# 1_MCU_IOBANK.net
KiCad netlist of a schematic drawn in Altium Designer
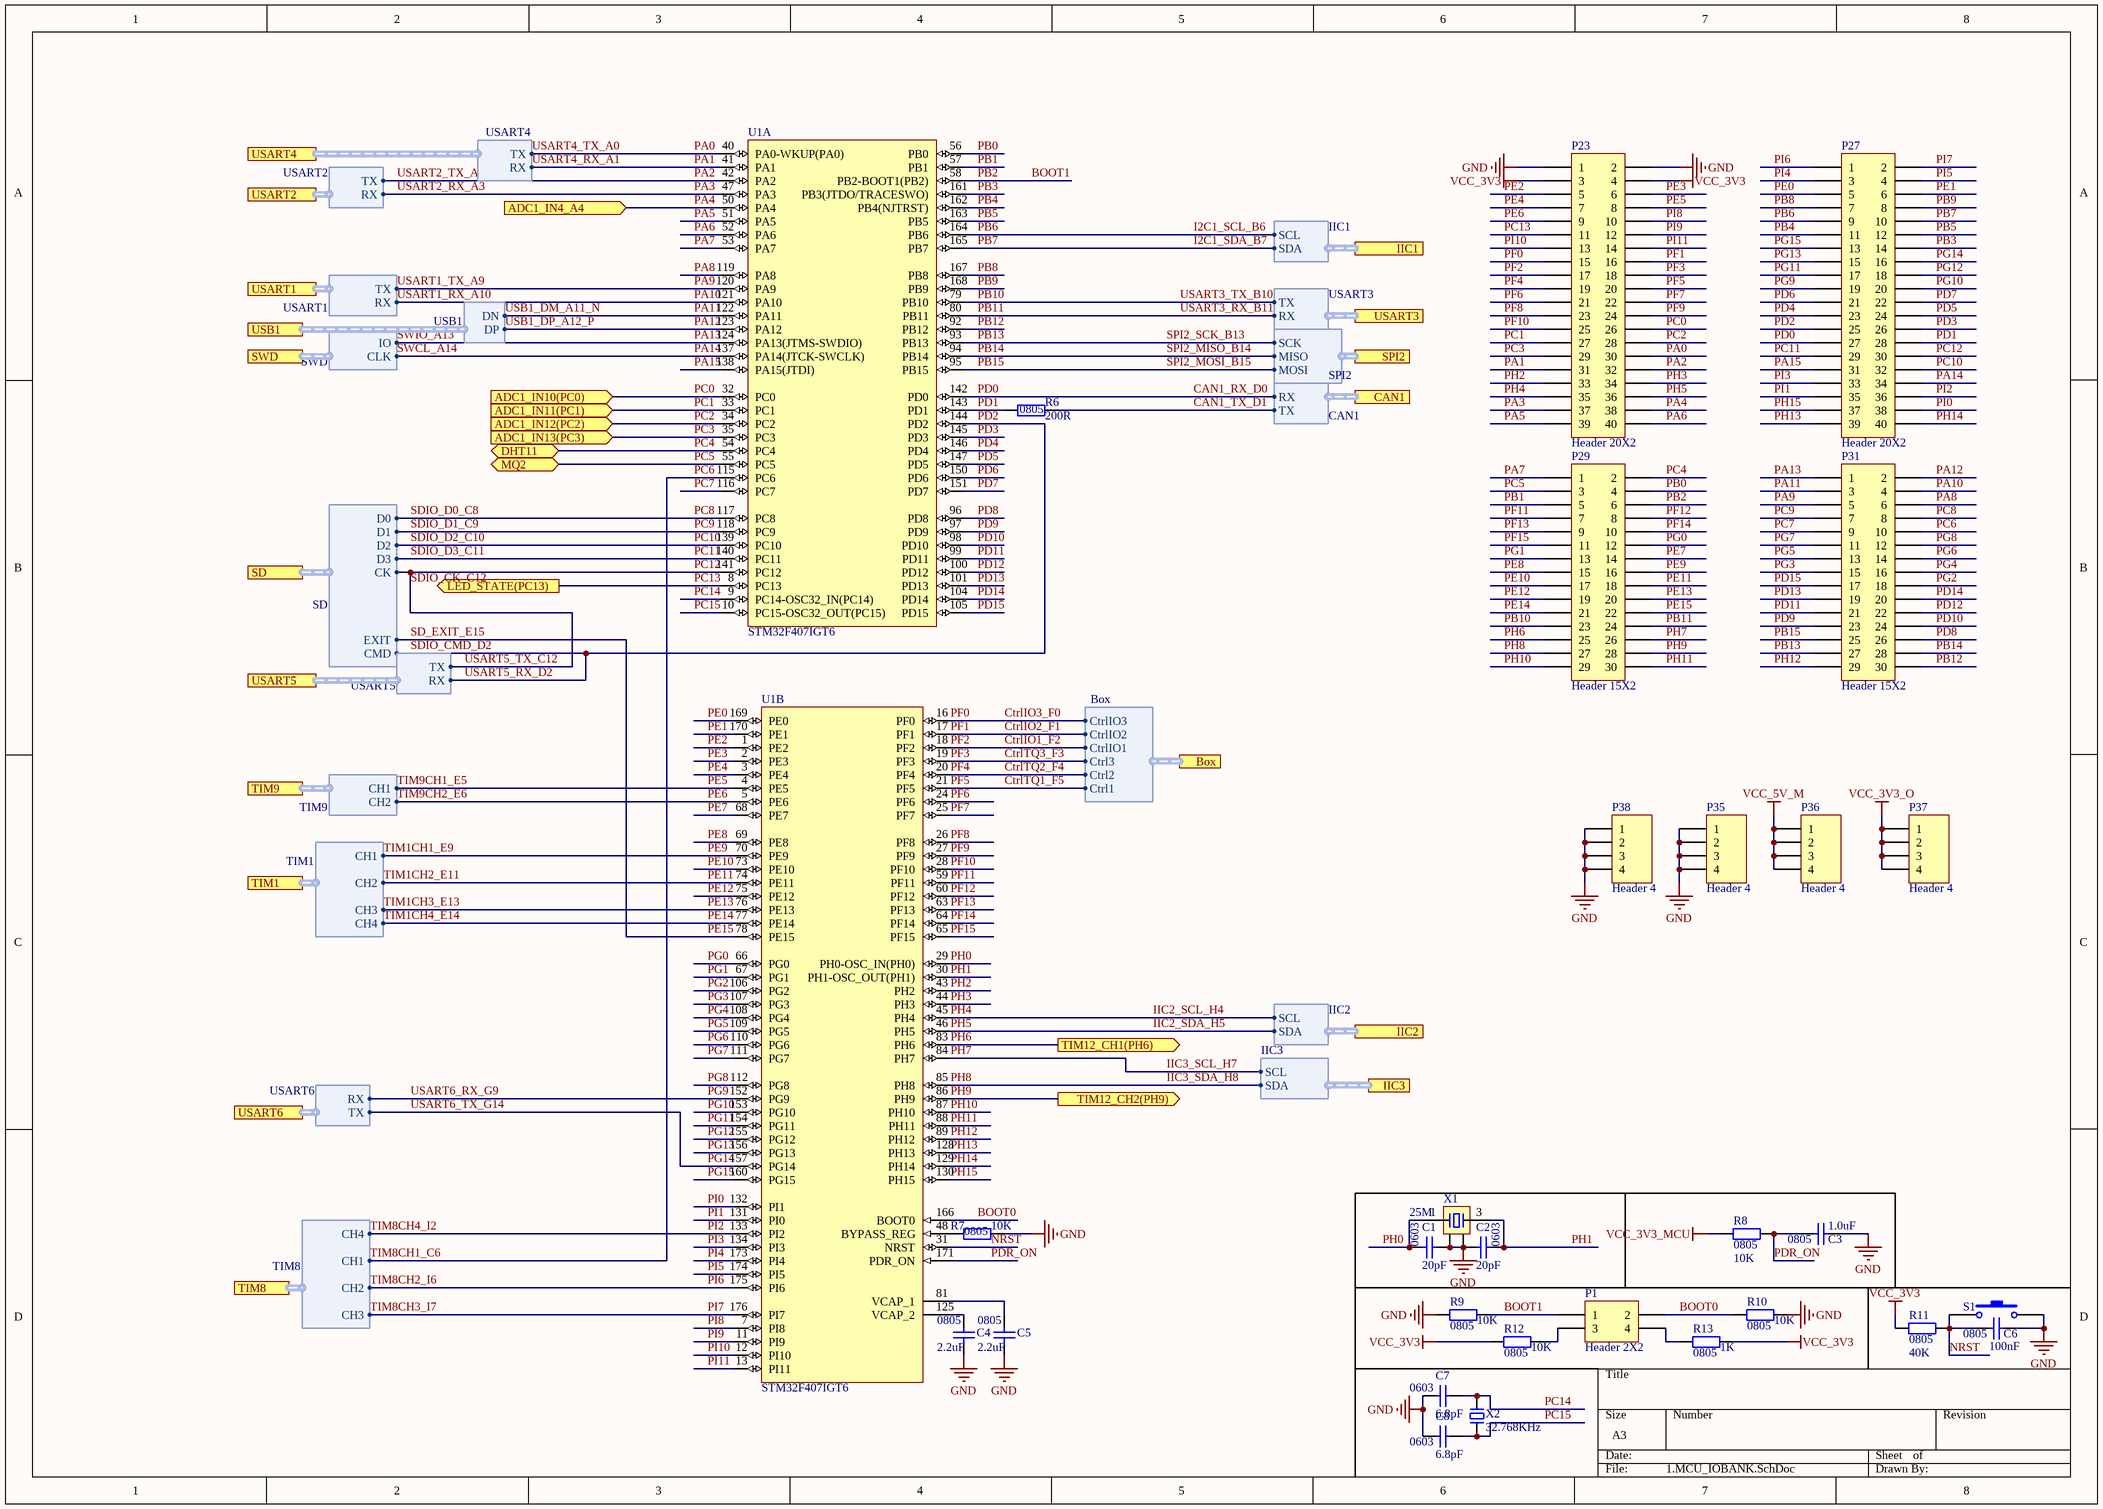
[diagram p0: 1.MCU_IOBANK.SchDoc]

(export (version "E")
  (design (tool "Eeschema 10.0.6"))
  (components
    (comp (ref "C1")
      (value "0603")
      (footprint "C 0603_L")
      (fields (field (name "ALTIUM_VALUE") "20pF"))
      (libsource (lib "QT") (part "CAP"))
    )
    (comp (ref "C2")
      (value "0603")
      (footprint "C 0603_L")
      (fields (field (name "ALTIUM_VALUE") "20pF"))
      (libsource (lib "QT") (part "CAP"))
    )
    (comp (ref "C3")
      (value "0805")
      (footprint "C 0805_M")
      (fields (field (name "ALTIUM_VALUE") "1.0uF"))
      (libsource (lib "QT") (part "CAP"))
    )
    (comp (ref "C4")
      (value "0805")
      (footprint "C 0805_M")
      (fields (field (name "ALTIUM_VALUE") "2.2uF"))
      (libsource (lib "QT") (part "CAP"))
    )
    (comp (ref "C5")
      (value "0805")
      (footprint "C 0805_M")
      (fields (field (name "ALTIUM_VALUE") "2.2uF"))
      (libsource (lib "QT") (part "CAP"))
    )
    (comp (ref "C6")
      (value "0805")
      (footprint "C 0805_M")
      (fields (field (name "ALTIUM_VALUE") "100nF"))
      (libsource (lib "QT") (part "CAP"))
    )
    (comp (ref "C7")
      (value "0603")
      (footprint "C 0603_M")
      (fields (field (name "ALTIUM_VALUE") "6.8pF"))
      (libsource (lib "QT") (part "CAP"))
    )
    (comp (ref "C8")
      (value "0603")
      (footprint "C 0603_L")
      (fields (field (name "ALTIUM_VALUE") "6.8pF"))
      (libsource (lib "QT") (part "CAP"))
    )
    (comp (ref "P1")
      (value "Header 2X2")
      (footprint "HDR2.54-LI-2x2P")
      (description "Header, 2-Pin, Dual row")
      (fields (field (name "PUBLISHER") "Altium Limited"))
      (libsource (lib "QT") (part "Header 2X2"))
    )
    (comp (ref "P23")
      (value "Header 20X2")
      (footprint "HDR2X20")
      (description "Header, 20-Pin, Dual row")
      (fields (field (name "PUBLISHER") "Altium Limited"))
      (libsource (lib "Miscellaneous Connectors") (part "Header 20X2"))
    )
    (comp (ref "P27")
      (value "Header 20X2")
      (footprint "HDR2X20")
      (description "Header, 20-Pin, Dual row")
      (fields (field (name "PUBLISHER") "Altium Limited"))
      (libsource (lib "Miscellaneous Connectors") (part "Header 20X2"))
    )
    (comp (ref "P29")
      (value "Header 15X2")
      (footprint "HDR2X15")
      (description "Header, 15-Pin, Dual row")
      (fields (field (name "PUBLISHER") "Altium Limited"))
      (libsource (lib "Miscellaneous Connectors") (part "Header 15X2"))
    )
    (comp (ref "P31")
      (value "Header 15X2")
      (footprint "HDR2X15")
      (description "Header, 15-Pin, Dual row")
      (fields (field (name "PUBLISHER") "Altium Limited"))
      (libsource (lib "Miscellaneous Connectors") (part "Header 15X2"))
    )
    (comp (ref "P35")
      (value "Header 4")
      (footprint "HDR2.54-LI-4P")
      (description "Header, 4-Pin")
      (fields (field (name "PUBLISHER") "Altium Limited"))
      (libsource (lib "QT") (part "Header 4"))
    )
    (comp (ref "P36")
      (value "Header 4")
      (footprint "HDR2.54-LI-4P")
      (description "Header, 4-Pin")
      (fields (field (name "PUBLISHER") "Altium Limited"))
      (libsource (lib "QT") (part "Header 4"))
    )
    (comp (ref "P37")
      (value "Header 4")
      (footprint "HDR2.54-LI-4P")
      (description "Header, 4-Pin")
      (fields (field (name "PUBLISHER") "Altium Limited"))
      (libsource (lib "QT") (part "Header 4"))
    )
    (comp (ref "P38")
      (value "Header 4")
      (footprint "HDR2.54-LI-4P")
      (description "Header, 4-Pin")
      (fields (field (name "PUBLISHER") "Altium Limited"))
      (libsource (lib "QT") (part "Header 4"))
    )
    (comp (ref "R6")
      (value "0805")
      (footprint "R 0805_L")
      (description "Resistor")
      (fields (field (name "ALTIUM_VALUE") "200R") (field (name "PUBLISHER") "Altium Limited"))
      (libsource (lib "QT") (part "RES2"))
    )
    (comp (ref "R7")
      (value "0805")
      (footprint "R 0805_L")
      (description "Resistor")
      (fields (field (name "ALTIUM_VALUE") "10K") (field (name "PUBLISHER") "Altium Limited"))
      (libsource (lib "QT") (part "RES2"))
    )
    (comp (ref "R8")
      (value "0805")
      (footprint "R 0805_L")
      (description "Resistor")
      (fields (field (name "ALTIUM_VALUE") "10K") (field (name "PUBLISHER") "Altium Limited"))
      (libsource (lib "QT") (part "RES2"))
    )
    (comp (ref "R9")
      (value "0805")
      (footprint "R 0805_L")
      (description "Resistor")
      (fields (field (name "ALTIUM_VALUE") "10K") (field (name "PUBLISHER") "Altium Limited"))
      (libsource (lib "QT") (part "RES2"))
    )
    (comp (ref "R10")
      (value "0805")
      (footprint "R 0805_L")
      (description "Resistor")
      (fields (field (name "ALTIUM_VALUE") "10K") (field (name "PUBLISHER") "Altium Limited"))
      (libsource (lib "QT") (part "RES2"))
    )
    (comp (ref "R11")
      (value "0805")
      (footprint "R 0805_L")
      (description "Resistor")
      (fields (field (name "ALTIUM_VALUE") "40K") (field (name "PUBLISHER") "Altium Limited"))
      (libsource (lib "QT") (part "RES2"))
    )
    (comp (ref "R12")
      (value "0805")
      (footprint "R 0805_L")
      (description "Resistor")
      (fields (field (name "ALTIUM_VALUE") "10K") (field (name "PUBLISHER") "Altium Limited"))
      (libsource (lib "QT") (part "RES2"))
    )
    (comp (ref "R13")
      (value "0805")
      (footprint "R 0805_L")
      (description "Resistor")
      (fields (field (name "ALTIUM_VALUE") "1K") (field (name "PUBLISHER") "Altium Limited"))
      (libsource (lib "QT") (part "RES2"))
    )
    (comp (ref "S1")
      (value "SW")
      (footprint "TSW DIP-3*6*5")
      (fields (field (name "PUBLISHER") "Altium Limited"))
      (libsource (lib "QT") (part "SW"))
    )
    (comp (ref "U1")
      (value "STM32F407IGT6")
      (footprint "STM-LQFP176_N")
      (fields (field (name "MANUFACTURER") "STMicroelectronics"))
      (libsource (lib "STMicroelectronics STM32 F4") (part "STM32F407IGT6"))
    )
    (comp (ref "X1")
      (value "25M")
      (footprint "XTAL-3225")
      (description "4脚晶振")
      (fields (field (name "版权归属") "源创客"))
      (libsource (lib "保险丝-晶振") (part "XTAL-4"))
    )
    (comp (ref "X2")
      (value "32.768KHz")
      (footprint "XTAL-3215A")
      (description "2脚晶振")
      (fields (field (name "版权归属") "源创客"))
      (libsource (lib "保险丝-晶振") (part "XTAL-2"))
    )
  )
  (nets
    (net (code "19") (name "/BOOT0") (class "Default")
      (node (ref "P1") (pin "2") (pinfunction "2_2") (pintype "passive"))
      (node (ref "R10") (pin "1") (pinfunction "1_1") (pintype "passive"))
      (node (ref "U1") (pin "166") (pinfunction "BOOT0_166") (pintype "input"))
    )
    (net (code "20") (name "/BOOT1") (class "Default")
      (node (ref "P1") (pin "1") (pinfunction "1_1") (pintype "passive"))
      (node (ref "P29") (pin "6") (pinfunction "6_6") (pintype "passive"))
      (node (ref "R9") (pin "2") (pinfunction "2_2") (pintype "passive"))
      (node (ref "U1") (pin "58") (pinfunction "PB2-BOOT1(PB2)_58") (pintype "bidirectional"))
    )
    (net (code "21") (name "/CAN1_RX_D0") (class "Default")
      (node (ref "P27") (pin "27") (pinfunction "27_27") (pintype "passive"))
      (node (ref "U1") (pin "142") (pinfunction "PD0_142") (pintype "bidirectional"))
    )
    (net (code "22") (name "/CAN1_TX_D1") (class "Default")
      (node (ref "R6") (pin "2") (pinfunction "2_2") (pintype "passive"))
    )
    (net (code "23") (name "/CtrlIO1_F2") (class "Default")
      (node (ref "P23") (pin "17") (pinfunction "17_17") (pintype "passive"))
      (node (ref "U1") (pin "18") (pinfunction "PF2_18") (pintype "bidirectional"))
    )
    (net (code "24") (name "/CtrlIO2_F1") (class "Default")
      (node (ref "P23") (pin "16") (pinfunction "16_16") (pintype "passive"))
      (node (ref "U1") (pin "17") (pinfunction "PF1_17") (pintype "bidirectional"))
    )
    (net (code "25") (name "/CtrlIO3_F0") (class "Default")
      (node (ref "P23") (pin "15") (pinfunction "15_15") (pintype "passive"))
      (node (ref "U1") (pin "16") (pinfunction "PF0_16") (pintype "bidirectional"))
    )
    (net (code "26") (name "/CtrlTQ1_F5") (class "Default")
      (node (ref "P23") (pin "20") (pinfunction "20_20") (pintype "passive"))
      (node (ref "U1") (pin "21") (pinfunction "PF5_21") (pintype "bidirectional"))
    )
    (net (code "27") (name "/CtrlTQ2_F4") (class "Default")
      (node (ref "P23") (pin "19") (pinfunction "19_19") (pintype "passive"))
      (node (ref "U1") (pin "20") (pinfunction "PF4_20") (pintype "bidirectional"))
    )
    (net (code "28") (name "/CtrlTQ3_F3") (class "Default")
      (node (ref "P23") (pin "18") (pinfunction "18_18") (pintype "passive"))
      (node (ref "U1") (pin "19") (pinfunction "PF3_19") (pintype "bidirectional"))
    )
    (net (code "29") (name "/I2C1_SCL_B6") (class "Default")
      (node (ref "P27") (pin "9") (pinfunction "9_9") (pintype "passive"))
      (node (ref "U1") (pin "164") (pinfunction "PB6_164") (pintype "bidirectional"))
    )
    (net (code "30") (name "/I2C1_SDA_B7") (class "Default")
      (node (ref "P27") (pin "10") (pinfunction "10_10") (pintype "passive"))
      (node (ref "U1") (pin "165") (pinfunction "PB7_165") (pintype "bidirectional"))
    )
    (net (code "31") (name "/IIC2_SCL_H4") (class "Default")
      (node (ref "P23") (pin "35") (pinfunction "35_35") (pintype "passive"))
      (node (ref "U1") (pin "45") (pinfunction "PH4_45") (pintype "bidirectional"))
    )
    (net (code "32") (name "/IIC2_SDA_H5") (class "Default")
      (node (ref "P23") (pin "36") (pinfunction "36_36") (pintype "passive"))
      (node (ref "U1") (pin "46") (pinfunction "PH5_46") (pintype "bidirectional"))
    )
    (net (code "33") (name "/IIC3_SCL_H7") (class "Default")
      (node (ref "P29") (pin "26") (pinfunction "26_26") (pintype "passive"))
      (node (ref "U1") (pin "84") (pinfunction "PH7_84") (pintype "bidirectional"))
    )
    (net (code "34") (name "/IIC3_SDA_H8") (class "Default")
      (node (ref "P29") (pin "27") (pinfunction "27_27") (pintype "passive"))
      (node (ref "U1") (pin "85") (pinfunction "PH8_85") (pintype "bidirectional"))
    )
    (net (code "35") (name "/NRST") (class "Default")
      (node (ref "C6") (pin "2") (pinfunction "2_2") (pintype "passive"))
      (node (ref "R11") (pin "2") (pinfunction "2_2") (pintype "passive"))
      (node (ref "S1") (pin "1") (pinfunction "1_1") (pintype "passive"))
      (node (ref "U1") (pin "31") (pinfunction "NRST_31") (pintype "bidirectional"))
    )
    (net (code "36") (name "/PA0") (class "Default")
      (node (ref "P23") (pin "30") (pinfunction "30_30") (pintype "passive"))
      (node (ref "U1") (pin "40") (pinfunction "PA0-WKUP(PA0)_40") (pintype "bidirectional"))
    )
    (net (code "37") (name "/PA1") (class "Default")
      (node (ref "P23") (pin "31") (pinfunction "31_31") (pintype "passive"))
      (node (ref "U1") (pin "41") (pinfunction "PA1_41") (pintype "bidirectional"))
    )
    (net (code "38") (name "/PA2") (class "Default")
      (node (ref "P23") (pin "32") (pinfunction "32_32") (pintype "passive"))
      (node (ref "U1") (pin "42") (pinfunction "PA2_42") (pintype "bidirectional"))
    )
    (net (code "39") (name "/PA3") (class "Default")
      (node (ref "P23") (pin "37") (pinfunction "37_37") (pintype "passive"))
      (node (ref "U1") (pin "47") (pinfunction "PA3_47") (pintype "bidirectional"))
    )
    (net (code "40") (name "/PA4") (class "Default")
      (node (ref "P23") (pin "38") (pinfunction "38_38") (pintype "passive"))
      (node (ref "U1") (pin "50") (pinfunction "PA4_50") (pintype "bidirectional"))
    )
    (net (code "41") (name "/PA5") (class "Default")
      (node (ref "P23") (pin "39") (pinfunction "39_39") (pintype "passive"))
      (node (ref "U1") (pin "51") (pinfunction "PA5_51") (pintype "bidirectional"))
    )
    (net (code "42") (name "/PA6") (class "Default")
      (node (ref "P23") (pin "40") (pinfunction "40_40") (pintype "passive"))
      (node (ref "U1") (pin "52") (pinfunction "PA6_52") (pintype "bidirectional"))
    )
    (net (code "43") (name "/PA7") (class "Default")
      (node (ref "P29") (pin "1") (pinfunction "1_1") (pintype "passive"))
      (node (ref "U1") (pin "53") (pinfunction "PA7_53") (pintype "bidirectional"))
    )
    (net (code "44") (name "/PA8") (class "Default")
      (node (ref "P31") (pin "6") (pinfunction "6_6") (pintype "passive"))
      (node (ref "U1") (pin "119") (pinfunction "PA8_119") (pintype "bidirectional"))
    )
    (net (code "45") (name "/PA9") (class "Default")
      (node (ref "P31") (pin "5") (pinfunction "5_5") (pintype "passive"))
      (node (ref "U1") (pin "120") (pinfunction "PA9_120") (pintype "bidirectional"))
    )
    (net (code "46") (name "/PA10") (class "Default")
      (node (ref "P31") (pin "4") (pinfunction "4_4") (pintype "passive"))
      (node (ref "U1") (pin "121") (pinfunction "PA10_121") (pintype "bidirectional"))
    )
    (net (code "47") (name "/PA11") (class "Default")
      (node (ref "P31") (pin "3") (pinfunction "3_3") (pintype "passive"))
      (node (ref "U1") (pin "122") (pinfunction "PA11_122") (pintype "bidirectional"))
    )
    (net (code "48") (name "/PA12") (class "Default")
      (node (ref "P31") (pin "2") (pinfunction "2_2") (pintype "passive"))
      (node (ref "U1") (pin "123") (pinfunction "PA12_123") (pintype "bidirectional"))
    )
    (net (code "49") (name "/PA13") (class "Default")
      (node (ref "P31") (pin "1") (pinfunction "1_1") (pintype "passive"))
      (node (ref "U1") (pin "124") (pinfunction "PA13(JTMS-SWDIO)_124") (pintype "bidirectional"))
    )
    (net (code "50") (name "/PA14") (class "Default")
      (node (ref "P27") (pin "34") (pinfunction "34_34") (pintype "passive"))
      (node (ref "U1") (pin "137") (pinfunction "PA14(JTCK-SWCLK)_137") (pintype "bidirectional"))
    )
    (net (code "51") (name "/PA15") (class "Default")
      (node (ref "P27") (pin "31") (pinfunction "31_31") (pintype "passive"))
      (node (ref "U1") (pin "138") (pinfunction "PA15(JTDI)_138") (pintype "bidirectional"))
    )
    (net (code "52") (name "/PB0") (class "Default")
      (node (ref "P29") (pin "4") (pinfunction "4_4") (pintype "passive"))
      (node (ref "U1") (pin "56") (pinfunction "PB0_56") (pintype "bidirectional"))
    )
    (net (code "53") (name "/PB1") (class "Default")
      (node (ref "P29") (pin "5") (pinfunction "5_5") (pintype "passive"))
      (node (ref "U1") (pin "57") (pinfunction "PB1_57") (pintype "bidirectional"))
    )
    (net (code "54") (name "/PB3") (class "Default")
      (node (ref "P27") (pin "14") (pinfunction "14_14") (pintype "passive"))
      (node (ref "U1") (pin "161") (pinfunction "PB3(JTDO/TRACESWO)_161") (pintype "bidirectional"))
    )
    (net (code "55") (name "/PB4") (class "Default")
      (node (ref "P27") (pin "11") (pinfunction "11_11") (pintype "passive"))
      (node (ref "U1") (pin "162") (pinfunction "PB4(NJTRST)_162") (pintype "bidirectional"))
    )
    (net (code "56") (name "/PB5") (class "Default")
      (node (ref "P27") (pin "12") (pinfunction "12_12") (pintype "passive"))
      (node (ref "U1") (pin "163") (pinfunction "PB5_163") (pintype "bidirectional"))
    )
    (net (code "57") (name "/PB8") (class "Default")
      (node (ref "P27") (pin "7") (pinfunction "7_7") (pintype "passive"))
      (node (ref "U1") (pin "167") (pinfunction "PB8_167") (pintype "bidirectional"))
    )
    (net (code "58") (name "/PB9") (class "Default")
      (node (ref "P27") (pin "8") (pinfunction "8_8") (pintype "passive"))
      (node (ref "U1") (pin "168") (pinfunction "PB9_168") (pintype "bidirectional"))
    )
    (net (code "59") (name "/PB10") (class "Default")
      (node (ref "P29") (pin "23") (pinfunction "23_23") (pintype "passive"))
      (node (ref "U1") (pin "79") (pinfunction "PB10_79") (pintype "bidirectional"))
    )
    (net (code "60") (name "/PB11") (class "Default")
      (node (ref "P29") (pin "24") (pinfunction "24_24") (pintype "passive"))
      (node (ref "U1") (pin "80") (pinfunction "PB11_80") (pintype "bidirectional"))
    )
    (net (code "61") (name "/PB12") (class "Default")
      (node (ref "P31") (pin "30") (pinfunction "30_30") (pintype "passive"))
      (node (ref "U1") (pin "92") (pinfunction "PB12_92") (pintype "bidirectional"))
    )
    (net (code "62") (name "/PB13") (class "Default")
      (node (ref "P31") (pin "27") (pinfunction "27_27") (pintype "passive"))
      (node (ref "U1") (pin "93") (pinfunction "PB13_93") (pintype "bidirectional"))
    )
    (net (code "63") (name "/PB14") (class "Default")
      (node (ref "P31") (pin "28") (pinfunction "28_28") (pintype "passive"))
      (node (ref "U1") (pin "94") (pinfunction "PB14_94") (pintype "bidirectional"))
    )
    (net (code "64") (name "/PB15") (class "Default")
      (node (ref "P31") (pin "25") (pinfunction "25_25") (pintype "passive"))
      (node (ref "U1") (pin "95") (pinfunction "PB15_95") (pintype "bidirectional"))
    )
    (net (code "65") (name "/PC0") (class "Default")
      (node (ref "P23") (pin "26") (pinfunction "26_26") (pintype "passive"))
      (node (ref "U1") (pin "32") (pinfunction "PC0_32") (pintype "bidirectional"))
    )
    (net (code "66") (name "/PC1") (class "Default")
      (node (ref "P23") (pin "27") (pinfunction "27_27") (pintype "passive"))
      (node (ref "U1") (pin "33") (pinfunction "PC1_33") (pintype "bidirectional"))
    )
    (net (code "67") (name "/PC2") (class "Default")
      (node (ref "P23") (pin "28") (pinfunction "28_28") (pintype "passive"))
      (node (ref "U1") (pin "34") (pinfunction "PC2_34") (pintype "bidirectional"))
    )
    (net (code "68") (name "/PC3") (class "Default")
      (node (ref "P23") (pin "29") (pinfunction "29_29") (pintype "passive"))
      (node (ref "U1") (pin "35") (pinfunction "PC3_35") (pintype "bidirectional"))
    )
    (net (code "69") (name "/PC4") (class "Default")
      (node (ref "P29") (pin "2") (pinfunction "2_2") (pintype "passive"))
      (node (ref "U1") (pin "54") (pinfunction "PC4_54") (pintype "bidirectional"))
    )
    (net (code "70") (name "/PC5") (class "Default")
      (node (ref "P29") (pin "3") (pinfunction "3_3") (pintype "passive"))
      (node (ref "U1") (pin "55") (pinfunction "PC5_55") (pintype "bidirectional"))
    )
    (net (code "71") (name "/PC6") (class "Default")
      (node (ref "P31") (pin "10") (pinfunction "10_10") (pintype "passive"))
      (node (ref "U1") (pin "115") (pinfunction "PC6_115") (pintype "bidirectional"))
    )
    (net (code "72") (name "/PC7") (class "Default")
      (node (ref "P31") (pin "9") (pinfunction "9_9") (pintype "passive"))
      (node (ref "U1") (pin "116") (pinfunction "PC7_116") (pintype "bidirectional"))
    )
    (net (code "73") (name "/PC8") (class "Default")
      (node (ref "P31") (pin "8") (pinfunction "8_8") (pintype "passive"))
      (node (ref "U1") (pin "117") (pinfunction "PC8_117") (pintype "bidirectional"))
    )
    (net (code "74") (name "/PC9") (class "Default")
      (node (ref "P31") (pin "7") (pinfunction "7_7") (pintype "passive"))
      (node (ref "U1") (pin "118") (pinfunction "PC9_118") (pintype "bidirectional"))
    )
    (net (code "75") (name "/PC10") (class "Default")
      (node (ref "P27") (pin "32") (pinfunction "32_32") (pintype "passive"))
      (node (ref "U1") (pin "139") (pinfunction "PC10_139") (pintype "bidirectional"))
    )
    (net (code "76") (name "/PC11") (class "Default")
      (node (ref "P27") (pin "29") (pinfunction "29_29") (pintype "passive"))
      (node (ref "U1") (pin "140") (pinfunction "PC11_140") (pintype "bidirectional"))
    )
    (net (code "77") (name "/PC12") (class "Default")
      (node (ref "P27") (pin "30") (pinfunction "30_30") (pintype "passive"))
      (node (ref "U1") (pin "141") (pinfunction "PC12_141") (pintype "bidirectional"))
    )
    (net (code "78") (name "/PC13") (class "Default")
      (node (ref "P23") (pin "11") (pinfunction "11_11") (pintype "passive"))
      (node (ref "U1") (pin "8") (pinfunction "PC13_8") (pintype "bidirectional"))
    )
    (net (code "79") (name "/PC14") (class "Default")
      (node (ref "C7") (pin "2") (pinfunction "2_2") (pintype "passive"))
      (node (ref "U1") (pin "9") (pinfunction "PC14-OSC32_IN(PC14)_9") (pintype "bidirectional"))
      (node (ref "X2") (pin "2") (pinfunction "2_2") (pintype "passive"))
    )
    (net (code "80") (name "/PC15") (class "Default")
      (node (ref "C8") (pin "2") (pinfunction "2_2") (pintype "passive"))
      (node (ref "U1") (pin "10") (pinfunction "PC15-OSC32_OUT(PC15)_10") (pintype "bidirectional"))
      (node (ref "X2") (pin "1") (pinfunction "1_1") (pintype "passive"))
    )
    (net (code "81") (name "/PD1") (class "Default")
      (node (ref "P27") (pin "28") (pinfunction "28_28") (pintype "passive"))
      (node (ref "R6") (pin "1") (pinfunction "1_1") (pintype "passive"))
      (node (ref "U1") (pin "143") (pinfunction "PD1_143") (pintype "bidirectional"))
    )
    (net (code "82") (name "/PD2") (class "Default")
      (node (ref "P27") (pin "25") (pinfunction "25_25") (pintype "passive"))
      (node (ref "U1") (pin "144") (pinfunction "PD2_144") (pintype "bidirectional"))
    )
    (net (code "83") (name "/PD3") (class "Default")
      (node (ref "P27") (pin "26") (pinfunction "26_26") (pintype "passive"))
      (node (ref "U1") (pin "145") (pinfunction "PD3_145") (pintype "bidirectional"))
    )
    (net (code "84") (name "/PD4") (class "Default")
      (node (ref "P27") (pin "23") (pinfunction "23_23") (pintype "passive"))
      (node (ref "U1") (pin "146") (pinfunction "PD4_146") (pintype "bidirectional"))
    )
    (net (code "85") (name "/PD5") (class "Default")
      (node (ref "P27") (pin "24") (pinfunction "24_24") (pintype "passive"))
      (node (ref "U1") (pin "147") (pinfunction "PD5_147") (pintype "bidirectional"))
    )
    (net (code "86") (name "/PD6") (class "Default")
      (node (ref "P27") (pin "21") (pinfunction "21_21") (pintype "passive"))
      (node (ref "U1") (pin "150") (pinfunction "PD6_150") (pintype "bidirectional"))
    )
    (net (code "87") (name "/PD7") (class "Default")
      (node (ref "P27") (pin "22") (pinfunction "22_22") (pintype "passive"))
      (node (ref "U1") (pin "151") (pinfunction "PD7_151") (pintype "bidirectional"))
    )
    (net (code "88") (name "/PD8") (class "Default")
      (node (ref "P31") (pin "26") (pinfunction "26_26") (pintype "passive"))
      (node (ref "U1") (pin "96") (pinfunction "PD8_96") (pintype "bidirectional"))
    )
    (net (code "89") (name "/PD9") (class "Default")
      (node (ref "P31") (pin "23") (pinfunction "23_23") (pintype "passive"))
      (node (ref "U1") (pin "97") (pinfunction "PD9_97") (pintype "bidirectional"))
    )
    (net (code "90") (name "/PD10") (class "Default")
      (node (ref "P31") (pin "24") (pinfunction "24_24") (pintype "passive"))
      (node (ref "U1") (pin "98") (pinfunction "PD10_98") (pintype "bidirectional"))
    )
    (net (code "91") (name "/PD11") (class "Default")
      (node (ref "P31") (pin "21") (pinfunction "21_21") (pintype "passive"))
      (node (ref "U1") (pin "99") (pinfunction "PD11_99") (pintype "bidirectional"))
    )
    (net (code "92") (name "/PD12") (class "Default")
      (node (ref "P31") (pin "22") (pinfunction "22_22") (pintype "passive"))
      (node (ref "U1") (pin "100") (pinfunction "PD12_100") (pintype "bidirectional"))
    )
    (net (code "93") (name "/PD13") (class "Default")
      (node (ref "P31") (pin "19") (pinfunction "19_19") (pintype "passive"))
      (node (ref "U1") (pin "101") (pinfunction "PD13_101") (pintype "bidirectional"))
    )
    (net (code "94") (name "/PD14") (class "Default")
      (node (ref "P31") (pin "20") (pinfunction "20_20") (pintype "passive"))
      (node (ref "U1") (pin "104") (pinfunction "PD14_104") (pintype "bidirectional"))
    )
    (net (code "95") (name "/PD15") (class "Default")
      (node (ref "P31") (pin "17") (pinfunction "17_17") (pintype "passive"))
      (node (ref "U1") (pin "105") (pinfunction "PD15_105") (pintype "bidirectional"))
    )
    (net (code "96") (name "/PDR_ON") (class "Default")
      (node (ref "C3") (pin "2") (pinfunction "2_2") (pintype "passive"))
      (node (ref "R8") (pin "2") (pinfunction "2_2") (pintype "passive"))
      (node (ref "U1") (pin "171") (pinfunction "PDR_ON_171") (pintype "input"))
    )
    (net (code "97") (name "/PE0") (class "Default")
      (node (ref "P27") (pin "5") (pinfunction "5_5") (pintype "passive"))
      (node (ref "U1") (pin "169") (pinfunction "PE0_169") (pintype "bidirectional"))
    )
    (net (code "98") (name "/PE1") (class "Default")
      (node (ref "P27") (pin "6") (pinfunction "6_6") (pintype "passive"))
      (node (ref "U1") (pin "170") (pinfunction "PE1_170") (pintype "bidirectional"))
    )
    (net (code "99") (name "/PE2") (class "Default")
      (node (ref "P23") (pin "5") (pinfunction "5_5") (pintype "passive"))
      (node (ref "U1") (pin "1") (pinfunction "PE2_1") (pintype "bidirectional"))
    )
    (net (code "100") (name "/PE3") (class "Default")
      (node (ref "P23") (pin "6") (pinfunction "6_6") (pintype "passive"))
      (node (ref "U1") (pin "2") (pinfunction "PE3_2") (pintype "bidirectional"))
    )
    (net (code "101") (name "/PE4") (class "Default")
      (node (ref "P23") (pin "7") (pinfunction "7_7") (pintype "passive"))
      (node (ref "U1") (pin "3") (pinfunction "PE4_3") (pintype "bidirectional"))
    )
    (net (code "102") (name "/PE5") (class "Default")
      (node (ref "P23") (pin "8") (pinfunction "8_8") (pintype "passive"))
      (node (ref "U1") (pin "4") (pinfunction "PE5_4") (pintype "bidirectional"))
    )
    (net (code "103") (name "/PE6") (class "Default")
      (node (ref "P23") (pin "9") (pinfunction "9_9") (pintype "passive"))
      (node (ref "U1") (pin "5") (pinfunction "PE6_5") (pintype "bidirectional"))
    )
    (net (code "104") (name "/PE7") (class "Default")
      (node (ref "P29") (pin "14") (pinfunction "14_14") (pintype "passive"))
      (node (ref "U1") (pin "68") (pinfunction "PE7_68") (pintype "bidirectional"))
    )
    (net (code "105") (name "/PE8") (class "Default")
      (node (ref "P29") (pin "15") (pinfunction "15_15") (pintype "passive"))
      (node (ref "U1") (pin "69") (pinfunction "PE8_69") (pintype "bidirectional"))
    )
    (net (code "106") (name "/PE9") (class "Default")
      (node (ref "P29") (pin "16") (pinfunction "16_16") (pintype "passive"))
      (node (ref "U1") (pin "70") (pinfunction "PE9_70") (pintype "bidirectional"))
    )
    (net (code "107") (name "/PE10") (class "Default")
      (node (ref "P29") (pin "17") (pinfunction "17_17") (pintype "passive"))
      (node (ref "U1") (pin "73") (pinfunction "PE10_73") (pintype "bidirectional"))
    )
    (net (code "108") (name "/PE11") (class "Default")
      (node (ref "P29") (pin "18") (pinfunction "18_18") (pintype "passive"))
      (node (ref "U1") (pin "74") (pinfunction "PE11_74") (pintype "bidirectional"))
    )
    (net (code "109") (name "/PE12") (class "Default")
      (node (ref "P29") (pin "19") (pinfunction "19_19") (pintype "passive"))
      (node (ref "U1") (pin "75") (pinfunction "PE12_75") (pintype "bidirectional"))
    )
    (net (code "110") (name "/PE13") (class "Default")
      (node (ref "P29") (pin "20") (pinfunction "20_20") (pintype "passive"))
      (node (ref "U1") (pin "76") (pinfunction "PE13_76") (pintype "bidirectional"))
    )
    (net (code "111") (name "/PE14") (class "Default")
      (node (ref "P29") (pin "21") (pinfunction "21_21") (pintype "passive"))
      (node (ref "U1") (pin "77") (pinfunction "PE14_77") (pintype "bidirectional"))
    )
    (net (code "112") (name "/PE15") (class "Default")
      (node (ref "P29") (pin "22") (pinfunction "22_22") (pintype "passive"))
      (node (ref "U1") (pin "78") (pinfunction "PE15_78") (pintype "bidirectional"))
    )
    (net (code "113") (name "/PF6") (class "Default")
      (node (ref "P23") (pin "21") (pinfunction "21_21") (pintype "passive"))
      (node (ref "U1") (pin "24") (pinfunction "PF6_24") (pintype "bidirectional"))
    )
    (net (code "114") (name "/PF7") (class "Default")
      (node (ref "P23") (pin "22") (pinfunction "22_22") (pintype "passive"))
      (node (ref "U1") (pin "25") (pinfunction "PF7_25") (pintype "bidirectional"))
    )
    (net (code "115") (name "/PF8") (class "Default")
      (node (ref "P23") (pin "23") (pinfunction "23_23") (pintype "passive"))
      (node (ref "U1") (pin "26") (pinfunction "PF8_26") (pintype "bidirectional"))
    )
    (net (code "116") (name "/PF9") (class "Default")
      (node (ref "P23") (pin "24") (pinfunction "24_24") (pintype "passive"))
      (node (ref "U1") (pin "27") (pinfunction "PF9_27") (pintype "bidirectional"))
    )
    (net (code "117") (name "/PF10") (class "Default")
      (node (ref "P23") (pin "25") (pinfunction "25_25") (pintype "passive"))
      (node (ref "U1") (pin "28") (pinfunction "PF10_28") (pintype "bidirectional"))
    )
    (net (code "118") (name "/PF11") (class "Default")
      (node (ref "P29") (pin "7") (pinfunction "7_7") (pintype "passive"))
      (node (ref "U1") (pin "59") (pinfunction "PF11_59") (pintype "bidirectional"))
    )
    (net (code "119") (name "/PF12") (class "Default")
      (node (ref "P29") (pin "8") (pinfunction "8_8") (pintype "passive"))
      (node (ref "U1") (pin "60") (pinfunction "PF12_60") (pintype "bidirectional"))
    )
    (net (code "120") (name "/PF13") (class "Default")
      (node (ref "P29") (pin "9") (pinfunction "9_9") (pintype "passive"))
      (node (ref "U1") (pin "63") (pinfunction "PF13_63") (pintype "bidirectional"))
    )
    (net (code "121") (name "/PF14") (class "Default")
      (node (ref "P29") (pin "10") (pinfunction "10_10") (pintype "passive"))
      (node (ref "U1") (pin "64") (pinfunction "PF14_64") (pintype "bidirectional"))
    )
    (net (code "122") (name "/PF15") (class "Default")
      (node (ref "P29") (pin "11") (pinfunction "11_11") (pintype "passive"))
      (node (ref "U1") (pin "65") (pinfunction "PF15_65") (pintype "bidirectional"))
    )
    (net (code "123") (name "/PG0") (class "Default")
      (node (ref "P29") (pin "12") (pinfunction "12_12") (pintype "passive"))
      (node (ref "U1") (pin "66") (pinfunction "PG0_66") (pintype "bidirectional"))
    )
    (net (code "124") (name "/PG1") (class "Default")
      (node (ref "P29") (pin "13") (pinfunction "13_13") (pintype "passive"))
      (node (ref "U1") (pin "67") (pinfunction "PG1_67") (pintype "bidirectional"))
    )
    (net (code "125") (name "/PG2") (class "Default")
      (node (ref "P31") (pin "18") (pinfunction "18_18") (pintype "passive"))
      (node (ref "U1") (pin "106") (pinfunction "PG2_106") (pintype "bidirectional"))
    )
    (net (code "126") (name "/PG3") (class "Default")
      (node (ref "P31") (pin "15") (pinfunction "15_15") (pintype "passive"))
      (node (ref "U1") (pin "107") (pinfunction "PG3_107") (pintype "bidirectional"))
    )
    (net (code "127") (name "/PG4") (class "Default")
      (node (ref "P31") (pin "16") (pinfunction "16_16") (pintype "passive"))
      (node (ref "U1") (pin "108") (pinfunction "PG4_108") (pintype "bidirectional"))
    )
    (net (code "128") (name "/PG5") (class "Default")
      (node (ref "P31") (pin "13") (pinfunction "13_13") (pintype "passive"))
      (node (ref "U1") (pin "109") (pinfunction "PG5_109") (pintype "bidirectional"))
    )
    (net (code "129") (name "/PG6") (class "Default")
      (node (ref "P31") (pin "14") (pinfunction "14_14") (pintype "passive"))
      (node (ref "U1") (pin "110") (pinfunction "PG6_110") (pintype "bidirectional"))
    )
    (net (code "130") (name "/PG7") (class "Default")
      (node (ref "P31") (pin "11") (pinfunction "11_11") (pintype "passive"))
      (node (ref "U1") (pin "111") (pinfunction "PG7_111") (pintype "bidirectional"))
    )
    (net (code "131") (name "/PG8") (class "Default")
      (node (ref "P31") (pin "12") (pinfunction "12_12") (pintype "passive"))
      (node (ref "U1") (pin "112") (pinfunction "PG8_112") (pintype "bidirectional"))
    )
    (net (code "132") (name "/PG9") (class "Default")
      (node (ref "P27") (pin "19") (pinfunction "19_19") (pintype "passive"))
      (node (ref "U1") (pin "152") (pinfunction "PG9_152") (pintype "bidirectional"))
    )
    (net (code "133") (name "/PG10") (class "Default")
      (node (ref "P27") (pin "20") (pinfunction "20_20") (pintype "passive"))
      (node (ref "U1") (pin "153") (pinfunction "PG10_153") (pintype "bidirectional"))
    )
    (net (code "134") (name "/PG11") (class "Default")
      (node (ref "P27") (pin "17") (pinfunction "17_17") (pintype "passive"))
      (node (ref "U1") (pin "154") (pinfunction "PG11_154") (pintype "bidirectional"))
    )
    (net (code "135") (name "/PG12") (class "Default")
      (node (ref "P27") (pin "18") (pinfunction "18_18") (pintype "passive"))
      (node (ref "U1") (pin "155") (pinfunction "PG12_155") (pintype "bidirectional"))
    )
    (net (code "136") (name "/PG13") (class "Default")
      (node (ref "P27") (pin "15") (pinfunction "15_15") (pintype "passive"))
      (node (ref "U1") (pin "156") (pinfunction "PG13_156") (pintype "bidirectional"))
    )
    (net (code "137") (name "/PG14") (class "Default")
      (node (ref "P27") (pin "16") (pinfunction "16_16") (pintype "passive"))
      (node (ref "U1") (pin "157") (pinfunction "PG14_157") (pintype "bidirectional"))
    )
    (net (code "138") (name "/PG15") (class "Default")
      (node (ref "P27") (pin "13") (pinfunction "13_13") (pintype "passive"))
      (node (ref "U1") (pin "160") (pinfunction "PG15_160") (pintype "bidirectional"))
    )
    (net (code "139") (name "/PH0") (class "Default")
      (node (ref "C1") (pin "1") (pinfunction "1_1") (pintype "passive"))
      (node (ref "U1") (pin "29") (pinfunction "PH0-OSC_IN(PH0)_29") (pintype "bidirectional"))
      (node (ref "X1") (pin "1") (pinfunction "1_1") (pintype "passive"))
    )
    (net (code "140") (name "/PH1") (class "Default")
      (node (ref "C2") (pin "2") (pinfunction "2_2") (pintype "passive"))
      (node (ref "U1") (pin "30") (pinfunction "PH1-OSC_OUT(PH1)_30") (pintype "bidirectional"))
      (node (ref "X1") (pin "3") (pinfunction "3_3") (pintype "passive"))
    )
    (net (code "141") (name "/PH2") (class "Default")
      (node (ref "P23") (pin "33") (pinfunction "33_33") (pintype "passive"))
      (node (ref "U1") (pin "43") (pinfunction "PH2_43") (pintype "bidirectional"))
    )
    (net (code "142") (name "/PH3") (class "Default")
      (node (ref "P23") (pin "34") (pinfunction "34_34") (pintype "passive"))
      (node (ref "U1") (pin "44") (pinfunction "PH3_44") (pintype "bidirectional"))
    )
    (net (code "143") (name "/PH6") (class "Default")
      (node (ref "P29") (pin "25") (pinfunction "25_25") (pintype "passive"))
      (node (ref "U1") (pin "83") (pinfunction "PH6_83") (pintype "bidirectional"))
    )
    (net (code "144") (name "/PH9") (class "Default")
      (node (ref "P29") (pin "28") (pinfunction "28_28") (pintype "passive"))
      (node (ref "U1") (pin "86") (pinfunction "PH9_86") (pintype "bidirectional"))
    )
    (net (code "145") (name "/PH10") (class "Default")
      (node (ref "P29") (pin "29") (pinfunction "29_29") (pintype "passive"))
      (node (ref "U1") (pin "87") (pinfunction "PH10_87") (pintype "bidirectional"))
    )
    (net (code "146") (name "/PH11") (class "Default")
      (node (ref "P29") (pin "30") (pinfunction "30_30") (pintype "passive"))
      (node (ref "U1") (pin "88") (pinfunction "PH11_88") (pintype "bidirectional"))
    )
    (net (code "147") (name "/PH12") (class "Default")
      (node (ref "P31") (pin "29") (pinfunction "29_29") (pintype "passive"))
      (node (ref "U1") (pin "89") (pinfunction "PH12_89") (pintype "bidirectional"))
    )
    (net (code "148") (name "/PH13") (class "Default")
      (node (ref "P27") (pin "39") (pinfunction "39_39") (pintype "passive"))
      (node (ref "U1") (pin "128") (pinfunction "PH13_128") (pintype "bidirectional"))
    )
    (net (code "149") (name "/PH14") (class "Default")
      (node (ref "P27") (pin "40") (pinfunction "40_40") (pintype "passive"))
      (node (ref "U1") (pin "129") (pinfunction "PH14_129") (pintype "bidirectional"))
    )
    (net (code "150") (name "/PH15") (class "Default")
      (node (ref "P27") (pin "37") (pinfunction "37_37") (pintype "passive"))
      (node (ref "U1") (pin "130") (pinfunction "PH15_130") (pintype "bidirectional"))
    )
    (net (code "151") (name "/PI0") (class "Default")
      (node (ref "P27") (pin "38") (pinfunction "38_38") (pintype "passive"))
      (node (ref "U1") (pin "132") (pinfunction "PI1_132") (pintype "bidirectional"))
    )
    (net (code "152") (name "/PI1") (class "Default")
      (node (ref "P27") (pin "35") (pinfunction "35_35") (pintype "passive"))
      (node (ref "U1") (pin "131") (pinfunction "PI0_131") (pintype "bidirectional"))
    )
    (net (code "153") (name "/PI2") (class "Default")
      (node (ref "P27") (pin "36") (pinfunction "36_36") (pintype "passive"))
      (node (ref "U1") (pin "133") (pinfunction "PI2_133") (pintype "bidirectional"))
    )
    (net (code "154") (name "/PI3") (class "Default")
      (node (ref "P27") (pin "33") (pinfunction "33_33") (pintype "passive"))
      (node (ref "U1") (pin "134") (pinfunction "PI3_134") (pintype "bidirectional"))
    )
    (net (code "155") (name "/PI4") (class "Default")
      (node (ref "P27") (pin "3") (pinfunction "3_3") (pintype "passive"))
      (node (ref "U1") (pin "173") (pinfunction "PI4_173") (pintype "bidirectional"))
    )
    (net (code "156") (name "/PI5") (class "Default")
      (node (ref "P27") (pin "4") (pinfunction "4_4") (pintype "passive"))
      (node (ref "U1") (pin "174") (pinfunction "PI5_174") (pintype "bidirectional"))
    )
    (net (code "157") (name "/PI6") (class "Default")
      (node (ref "P27") (pin "1") (pinfunction "1_1") (pintype "passive"))
      (node (ref "U1") (pin "175") (pinfunction "PI6_175") (pintype "bidirectional"))
    )
    (net (code "158") (name "/PI7") (class "Default")
      (node (ref "P27") (pin "2") (pinfunction "2_2") (pintype "passive"))
      (node (ref "U1") (pin "176") (pinfunction "PI7_176") (pintype "bidirectional"))
    )
    (net (code "159") (name "/PI8") (class "Default")
      (node (ref "P23") (pin "10") (pinfunction "10_10") (pintype "passive"))
      (node (ref "U1") (pin "7") (pinfunction "PI8_7") (pintype "bidirectional"))
    )
    (net (code "160") (name "/PI9") (class "Default")
      (node (ref "P23") (pin "12") (pinfunction "12_12") (pintype "passive"))
      (node (ref "U1") (pin "11") (pinfunction "PI9_11") (pintype "bidirectional"))
    )
    (net (code "161") (name "/PI10") (class "Default")
      (node (ref "P23") (pin "13") (pinfunction "13_13") (pintype "passive"))
      (node (ref "U1") (pin "12") (pinfunction "PI10_12") (pintype "bidirectional"))
    )
    (net (code "162") (name "/PI11") (class "Default")
      (node (ref "P23") (pin "14") (pinfunction "14_14") (pintype "passive"))
      (node (ref "U1") (pin "13") (pinfunction "PI11_13") (pintype "bidirectional"))
    )
    (net (code "181") (name "GND") (class "Default")
      (node (ref "C1") (pin "2") (pinfunction "2_2") (pintype "passive"))
      (node (ref "C2") (pin "1") (pinfunction "1_1") (pintype "passive"))
      (node (ref "C3") (pin "1") (pinfunction "1_1") (pintype "passive"))
      (node (ref "C4") (pin "1") (pinfunction "1_1") (pintype "passive"))
      (node (ref "C5") (pin "1") (pinfunction "1_1") (pintype "passive"))
      (node (ref "C6") (pin "1") (pinfunction "1_1") (pintype "passive"))
      (node (ref "C7") (pin "1") (pinfunction "1_1") (pintype "passive"))
      (node (ref "C8") (pin "1") (pinfunction "1_1") (pintype "passive"))
      (node (ref "P23") (pin "1") (pinfunction "1_1") (pintype "passive"))
      (node (ref "P23") (pin "2") (pinfunction "2_2") (pintype "passive"))
      (node (ref "P35") (pin "1") (pinfunction "1_1") (pintype "passive"))
      (node (ref "P35") (pin "2") (pinfunction "2_2") (pintype "passive"))
      (node (ref "P35") (pin "3") (pinfunction "3_3") (pintype "passive"))
      (node (ref "P35") (pin "4") (pinfunction "4_4") (pintype "passive"))
      (node (ref "P38") (pin "1") (pinfunction "1_1") (pintype "passive"))
      (node (ref "P38") (pin "2") (pinfunction "2_2") (pintype "passive"))
      (node (ref "P38") (pin "3") (pinfunction "3_3") (pintype "passive"))
      (node (ref "P38") (pin "4") (pinfunction "4_4") (pintype "passive"))
      (node (ref "R10") (pin "2") (pinfunction "2_2") (pintype "passive"))
      (node (ref "R7") (pin "2") (pinfunction "2_2") (pintype "passive"))
      (node (ref "R9") (pin "1") (pinfunction "1_1") (pintype "passive"))
      (node (ref "S1") (pin "2") (pinfunction "2_2") (pintype "passive"))
      (node (ref "X1") (pin "2") (pinfunction "2_2") (pintype "passive"))
      (node (ref "X1") (pin "4") (pinfunction "4_4") (pintype "passive"))
    )
    (net (code "182") (name "Net-(P1-Pad3)") (class "Default")
      (node (ref "P1") (pin "3") (pinfunction "3_3") (pintype "passive"))
      (node (ref "R12") (pin "2") (pinfunction "2_2") (pintype "passive"))
    )
    (net (code "183") (name "Net-(P1-Pad4)") (class "Default")
      (node (ref "P1") (pin "4") (pinfunction "4_4") (pintype "passive"))
      (node (ref "R13") (pin "1") (pinfunction "1_1") (pintype "passive"))
    )
    (net (code "184") (name "Net-(U1B-BYPASS_REG)") (class "Default")
      (node (ref "R7") (pin "1") (pinfunction "1_1") (pintype "passive"))
      (node (ref "U1") (pin "48") (pinfunction "BYPASS_REG_48") (pintype "input"))
    )
    (net (code "185") (name "Net-(U1B-VCAP_1)") (class "Default")
      (node (ref "C5") (pin "2") (pinfunction "2_2") (pintype "passive"))
      (node (ref "U1") (pin "81") (pinfunction "VCAP_1_81") (pintype "power_in"))
    )
    (net (code "186") (name "Net-(U1B-VCAP_2)") (class "Default")
      (node (ref "C4") (pin "2") (pinfunction "2_2") (pintype "passive"))
      (node (ref "U1") (pin "125") (pinfunction "VCAP_2_125") (pintype "power_in"))
    )
    (net (code "187") (name "VCC_3V3") (class "Default")
      (node (ref "P23") (pin "3") (pinfunction "3_3") (pintype "passive"))
      (node (ref "P23") (pin "4") (pinfunction "4_4") (pintype "passive"))
      (node (ref "R11") (pin "1") (pinfunction "1_1") (pintype "passive"))
      (node (ref "R12") (pin "1") (pinfunction "1_1") (pintype "passive"))
      (node (ref "R13") (pin "2") (pinfunction "2_2") (pintype "passive"))
    )
    (net (code "188") (name "VCC_3V3_MCU") (class "Default")
      (node (ref "R8") (pin "1") (pinfunction "1_1") (pintype "passive"))
    )
    (net (code "189") (name "VCC_3V3_O") (class "Default")
      (node (ref "P37") (pin "1") (pinfunction "1_1") (pintype "passive"))
      (node (ref "P37") (pin "2") (pinfunction "2_2") (pintype "passive"))
      (node (ref "P37") (pin "3") (pinfunction "3_3") (pintype "passive"))
      (node (ref "P37") (pin "4") (pinfunction "4_4") (pintype "passive"))
    )
    (net (code "190") (name "VCC_5V_M") (class "Default")
      (node (ref "P36") (pin "1") (pinfunction "1_1") (pintype "passive"))
      (node (ref "P36") (pin "2") (pinfunction "2_2") (pintype "passive"))
      (node (ref "P36") (pin "3") (pinfunction "3_3") (pintype "passive"))
      (node (ref "P36") (pin "4") (pinfunction "4_4") (pintype "passive"))
    )
  )
)
